# Teensy_PCB.net
KiCad netlist of a schematic drawn in EAGLE
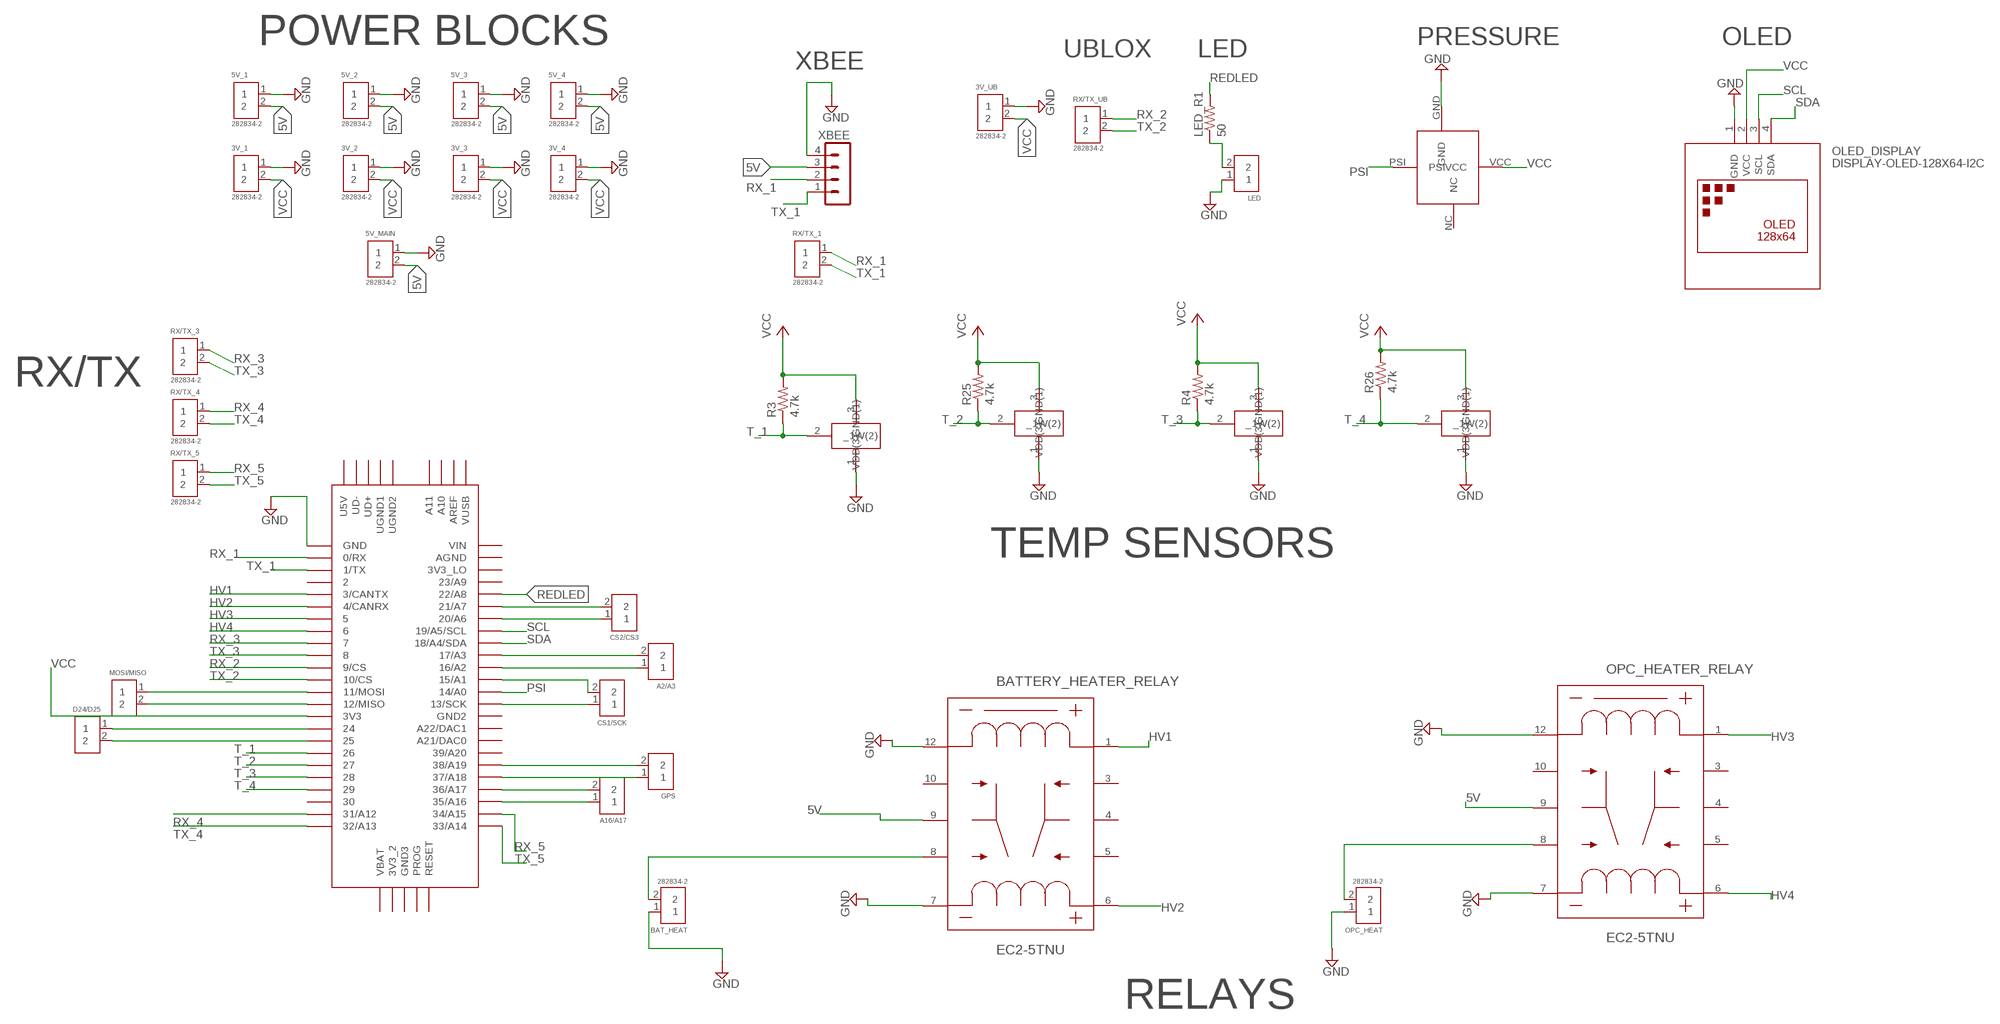
[diagram p0: schematic, sheet 1]

(export (version "E")
  (design (tool "Eeschema 10.0.6"))
  (components
    (comp (ref "3V_1")
      (value "282834-2")
      (footprint "eagle-import:CONN_282834-2")
      (fields (field (name "DIGI-KEY_PART_NUMBER") "A98333-ND") (field (name "MF") "TE Connectivity"))
      (libsource (lib "eagle-import") (part "282834-2"))
    )
    (comp (ref "3V_2")
      (value "282834-2")
      (footprint "eagle-import:CONN_282834-2")
      (fields (field (name "DIGI-KEY_PART_NUMBER") "A98333-ND") (field (name "MF") "TE Connectivity"))
      (libsource (lib "eagle-import") (part "282834-2"))
    )
    (comp (ref "3V_3")
      (value "282834-2")
      (footprint "eagle-import:CONN_282834-2")
      (fields (field (name "DIGI-KEY_PART_NUMBER") "A98333-ND") (field (name "MF") "TE Connectivity"))
      (libsource (lib "eagle-import") (part "282834-2"))
    )
    (comp (ref "3V_4")
      (value "282834-2")
      (footprint "eagle-import:CONN_282834-2")
      (fields (field (name "DIGI-KEY_PART_NUMBER") "A98333-ND") (field (name "MF") "TE Connectivity"))
      (libsource (lib "eagle-import") (part "282834-2"))
    )
    (comp (ref "3V_UB")
      (value "282834-2")
      (footprint "eagle-import:CONN_282834-2")
      (fields (field (name "DIGI-KEY_PART_NUMBER") "A98333-ND") (field (name "MF") "TE Connectivity"))
      (libsource (lib "eagle-import") (part "282834-2"))
    )
    (comp (ref "5V_1")
      (value "282834-2")
      (footprint "eagle-import:CONN_282834-2")
      (fields (field (name "DIGI-KEY_PART_NUMBER") "A98333-ND") (field (name "MF") "TE Connectivity"))
      (libsource (lib "eagle-import") (part "282834-2"))
    )
    (comp (ref "5V_2")
      (value "282834-2")
      (footprint "eagle-import:CONN_282834-2")
      (fields (field (name "DIGI-KEY_PART_NUMBER") "A98333-ND") (field (name "MF") "TE Connectivity"))
      (libsource (lib "eagle-import") (part "282834-2"))
    )
    (comp (ref "5V_3")
      (value "282834-2")
      (footprint "eagle-import:CONN_282834-2")
      (fields (field (name "DIGI-KEY_PART_NUMBER") "A98333-ND") (field (name "MF") "TE Connectivity"))
      (libsource (lib "eagle-import") (part "282834-2"))
    )
    (comp (ref "5V_4")
      (value "282834-2")
      (footprint "eagle-import:CONN_282834-2")
      (fields (field (name "DIGI-KEY_PART_NUMBER") "A98333-ND") (field (name "MF") "TE Connectivity"))
      (libsource (lib "eagle-import") (part "282834-2"))
    )
    (comp (ref "5V_MAIN")
      (value "282834-2")
      (footprint "eagle-import:CONN_282834-2")
      (fields (field (name "DIGI-KEY_PART_NUMBER") "A98333-ND") (field (name "MF") "TE Connectivity"))
      (libsource (lib "eagle-import") (part "282834-2"))
    )
    (comp (ref "A2/A3")
      (value "282834-2")
      (footprint "eagle-import:CONN_282834-2")
      (fields (field (name "DIGI-KEY_PART_NUMBER") "A98333-ND") (field (name "MF") "TE Connectivity"))
      (libsource (lib "eagle-import") (part "282834-2"))
    )
    (comp (ref "A16/A17")
      (value "282834-2")
      (footprint "eagle-import:CONN_282834-2")
      (fields (field (name "DIGI-KEY_PART_NUMBER") "A98333-ND") (field (name "MF") "TE Connectivity"))
      (libsource (lib "eagle-import") (part "282834-2"))
    )
    (comp (ref "BATTERY_HEATER_RELAY")
      (value "EC2-5TNU")
      (footprint "eagle-import:EC2TNU")
      (fields (field (name "MANUFACTURER_PART_NUMBER") "EC25TNU"))
      (libsource (lib "eagle-import") (part "EC2-5TNU"))
    )
    (comp (ref "BAT_HEAT")
      (value "282834-2")
      (footprint "eagle-import:CONN_282834-2")
      (fields (field (name "DIGI-KEY_PART_NUMBER") "A98333-ND") (field (name "MF") "TE Connectivity"))
      (libsource (lib "eagle-import") (part "282834-2"))
    )
    (comp (ref "CS1/SCK")
      (value "282834-2")
      (footprint "eagle-import:CONN_282834-2")
      (fields (field (name "DIGI-KEY_PART_NUMBER") "A98333-ND") (field (name "MF") "TE Connectivity"))
      (libsource (lib "eagle-import") (part "282834-2"))
    )
    (comp (ref "CS2/CS3")
      (value "282834-2")
      (footprint "eagle-import:CONN_282834-2")
      (fields (field (name "DIGI-KEY_PART_NUMBER") "A98333-ND") (field (name "MF") "TE Connectivity"))
      (libsource (lib "eagle-import") (part "282834-2"))
    )
    (comp (ref "D24/D25")
      (value "282834-2")
      (footprint "eagle-import:CONN_282834-2")
      (fields (field (name "DIGI-KEY_PART_NUMBER") "A98333-ND") (field (name "MF") "TE Connectivity"))
      (libsource (lib "eagle-import") (part "282834-2"))
    )
    (comp (ref "GPS")
      (value "282834-2")
      (footprint "eagle-import:CONN_282834-2")
      (fields (field (name "DIGI-KEY_PART_NUMBER") "A98333-ND") (field (name "MF") "TE Connectivity"))
      (libsource (lib "eagle-import") (part "282834-2"))
    )
    (comp (ref "LED")
      (value "282834-2")
      (footprint "eagle-import:CONN_282834-2")
      (fields (field (name "DIGI-KEY_PART_NUMBER") "A98333-ND") (field (name "MF") "TE Connectivity"))
      (libsource (lib "eagle-import") (part "282834-2"))
    )
    (comp (ref "LED_R1")
      (value "50")
      (footprint "eagle-import:0204_7")
      (libsource (lib "eagle-import") (part "R-US_0204/7"))
    )
    (comp (ref "MOSI/MISO")
      (value "282834-2")
      (footprint "eagle-import:CONN_282834-2")
      (fields (field (name "DIGI-KEY_PART_NUMBER") "A98333-ND") (field (name "MF") "TE Connectivity"))
      (libsource (lib "eagle-import") (part "282834-2"))
    )
    (comp (ref "OLED_DISPLAY")
      (value "DISPLAY-OLED-128X64-I2C")
      (footprint "eagle-import:DISPLAY-OLED-128X64-I2C")
      (libsource (lib "eagle-import") (part "DISPLAY-OLED-128X64-I2C"))
    )
    (comp (ref "OPC_HEAT")
      (value "282834-2")
      (footprint "eagle-import:CONN_282834-2")
      (fields (field (name "DIGI-KEY_PART_NUMBER") "A98333-ND") (field (name "MF") "TE Connectivity"))
      (libsource (lib "eagle-import") (part "282834-2"))
    )
    (comp (ref "OPC_HEATER_RELAY")
      (value "EC2-5TNU")
      (footprint "eagle-import:EC2TNU")
      (fields (field (name "MANUFACTURER_PART_NUMBER") "EC25TNU"))
      (libsource (lib "eagle-import") (part "EC2-5TNU"))
    )
    (comp (ref "PRESSURE_SENSOR")
      (value "SSCSANN015PAAA5")
      (footprint "eagle-import:SSCSANN015PAAA5")
      (libsource (lib "eagle-import") (part "SSCSANN015PAAA5"))
    )
    (comp (ref "R3")
      (value "4.7k")
      (footprint "eagle-import:0204_7")
      (libsource (lib "eagle-import") (part "R-US_0204/7"))
    )
    (comp (ref "R4")
      (value "4.7k")
      (footprint "eagle-import:0204_7")
      (libsource (lib "eagle-import") (part "R-US_0204/7"))
    )
    (comp (ref "R25")
      (value "4.7k")
      (footprint "eagle-import:0204_7")
      (libsource (lib "eagle-import") (part "R-US_0204/7"))
    )
    (comp (ref "R26")
      (value "4.7k")
      (footprint "eagle-import:0204_7")
      (libsource (lib "eagle-import") (part "R-US_0204/7"))
    )
    (comp (ref "RX/TX_1")
      (value "282834-2")
      (footprint "eagle-import:CONN_282834-2")
      (fields (field (name "DIGI-KEY_PART_NUMBER") "A98333-ND") (field (name "MF") "TE Connectivity"))
      (libsource (lib "eagle-import") (part "282834-2"))
    )
    (comp (ref "RX/TX_3")
      (value "282834-2")
      (footprint "eagle-import:CONN_282834-2")
      (fields (field (name "DIGI-KEY_PART_NUMBER") "A98333-ND") (field (name "MF") "TE Connectivity"))
      (libsource (lib "eagle-import") (part "282834-2"))
    )
    (comp (ref "RX/TX_4")
      (value "282834-2")
      (footprint "eagle-import:CONN_282834-2")
      (fields (field (name "DIGI-KEY_PART_NUMBER") "A98333-ND") (field (name "MF") "TE Connectivity"))
      (libsource (lib "eagle-import") (part "282834-2"))
    )
    (comp (ref "RX/TX_5")
      (value "282834-2")
      (footprint "eagle-import:CONN_282834-2")
      (fields (field (name "DIGI-KEY_PART_NUMBER") "A98333-ND") (field (name "MF") "TE Connectivity"))
      (libsource (lib "eagle-import") (part "282834-2"))
    )
    (comp (ref "RX/TX_UB")
      (value "282834-2")
      (footprint "eagle-import:CONN_282834-2")
      (fields (field (name "DIGI-KEY_PART_NUMBER") "A98333-ND") (field (name "MF") "TE Connectivity"))
      (libsource (lib "eagle-import") (part "282834-2"))
    )
    (comp (ref "TEMP_1")
      (value "DS18B20.2")
      (footprint "eagle-import:TO92-")
      (libsource (lib "eagle-import") (part "DS18B20.2"))
    )
    (comp (ref "TEMP_2")
      (value "DS18B20.2")
      (footprint "eagle-import:TO92-")
      (libsource (lib "eagle-import") (part "DS18B20.2"))
    )
    (comp (ref "TEMP_3")
      (value "DS18B20.2")
      (footprint "eagle-import:TO92-")
      (libsource (lib "eagle-import") (part "DS18B20.2"))
    )
    (comp (ref "TEMP_4")
      (value "DS18B20.2")
      (footprint "eagle-import:TO92-")
      (libsource (lib "eagle-import") (part "DS18B20.2"))
    )
    (comp (ref "U$1")
      (value "TEENSY_3.5/3.6")
      (footprint "eagle-import:TEENSY_3.5_3.6")
      (libsource (lib "eagle-import") (part "TEENSY_3.5/3.6"))
    )
    (comp (ref "XBEE")
      (value "MA04-1")
      (footprint "eagle-import:MA04-1")
      (libsource (lib "eagle-import") (part "MA04-1"))
    )
  )
  (nets
    (net (code "1") (name "/HV1") (class "Default")
      (node (ref "BATTERY_HEATER_RELAY") (pin "1") (pinfunction "1_1") (pintype "passive"))
      (node (ref "U$1") (pin "3/CANTX") (pinfunction "3/CANTX_3/CANTX") (pintype "bidirectional"))
    )
    (net (code "2") (name "/HV2") (class "Default")
      (node (ref "BATTERY_HEATER_RELAY") (pin "6") (pinfunction "5_6") (pintype "passive"))
      (node (ref "U$1") (pin "4/CANRX") (pinfunction "4/CANRX_4/CANRX") (pintype "bidirectional"))
    )
    (net (code "3") (name "/HV3") (class "Default")
      (node (ref "OPC_HEATER_RELAY") (pin "1") (pinfunction "1_1") (pintype "passive"))
      (node (ref "U$1") (pin "5") (pinfunction "5_5") (pintype "bidirectional"))
    )
    (net (code "4") (name "/HV4") (class "Default")
      (node (ref "OPC_HEATER_RELAY") (pin "6") (pinfunction "5_6") (pintype "passive"))
      (node (ref "U$1") (pin "6") (pinfunction "6_6") (pintype "bidirectional"))
    )
    (net (code "5") (name "/PSI") (class "Default")
      (node (ref "PRESSURE_SENSOR") (pin "PSI") (pinfunction "PSI_PSI") (pintype "bidirectional"))
      (node (ref "U$1") (pin "14/A0") (pinfunction "14/A0_14/A0") (pintype "bidirectional"))
    )
    (net (code "6") (name "/RX_1") (class "Default")
      (node (ref "RX/TX_1") (pin "1") (pinfunction "1_1") (pintype "passive"))
      (node (ref "U$1") (pin "0/RX") (pinfunction "0/RX_0/RX") (pintype "bidirectional"))
      (node (ref "XBEE") (pin "2") (pinfunction "2_2") (pintype "passive"))
    )
    (net (code "7") (name "/RX_2") (class "Default")
      (node (ref "RX/TX_UB") (pin "1") (pinfunction "1_1") (pintype "passive"))
      (node (ref "U$1") (pin "9/CS") (pinfunction "9/CS_9/CS") (pintype "bidirectional"))
    )
    (net (code "8") (name "/RX_3") (class "Default")
      (node (ref "RX/TX_3") (pin "1") (pinfunction "1_1") (pintype "passive"))
      (node (ref "U$1") (pin "7") (pinfunction "7_7") (pintype "bidirectional"))
    )
    (net (code "9") (name "/RX_4") (class "Default")
      (node (ref "RX/TX_4") (pin "1") (pinfunction "1_1") (pintype "passive"))
      (node (ref "U$1") (pin "31/A12") (pinfunction "31/A12_31/A12") (pintype "bidirectional"))
    )
    (net (code "10") (name "/RX_5") (class "Default")
      (node (ref "RX/TX_5") (pin "1") (pinfunction "1_1") (pintype "passive"))
      (node (ref "U$1") (pin "34/A15") (pinfunction "34/A15_34/A15") (pintype "bidirectional"))
    )
    (net (code "11") (name "/SCL") (class "Default")
      (node (ref "OLED_DISPLAY") (pin "3") (pinfunction "SCL_3") (pintype "bidirectional"))
      (node (ref "U$1") (pin "19/A5/SCL") (pinfunction "19/A5/SCL_19/A5/SCL") (pintype "bidirectional"))
    )
    (net (code "12") (name "/SDA") (class "Default")
      (node (ref "OLED_DISPLAY") (pin "4") (pinfunction "SDA_4") (pintype "bidirectional"))
      (node (ref "U$1") (pin "18/A4/SDA") (pinfunction "18/A4/SDA_18/A4/SDA") (pintype "bidirectional"))
    )
    (net (code "13") (name "/TX_1") (class "Default")
      (node (ref "RX/TX_1") (pin "2") (pinfunction "2_2") (pintype "passive"))
      (node (ref "U$1") (pin "1/TX") (pinfunction "1/TX_1/TX") (pintype "bidirectional"))
      (node (ref "XBEE") (pin "1") (pinfunction "1_1") (pintype "passive"))
    )
    (net (code "14") (name "/TX_2") (class "Default")
      (node (ref "RX/TX_UB") (pin "2") (pinfunction "2_2") (pintype "passive"))
      (node (ref "U$1") (pin "10/CS") (pinfunction "10/CS_10/CS") (pintype "bidirectional"))
    )
    (net (code "15") (name "/TX_3") (class "Default")
      (node (ref "RX/TX_3") (pin "2") (pinfunction "2_2") (pintype "passive"))
      (node (ref "U$1") (pin "8") (pinfunction "8_8") (pintype "bidirectional"))
    )
    (net (code "16") (name "/TX_4") (class "Default")
      (node (ref "RX/TX_4") (pin "2") (pinfunction "2_2") (pintype "passive"))
      (node (ref "U$1") (pin "32/A13") (pinfunction "32/A13_32/A13") (pintype "bidirectional"))
    )
    (net (code "17") (name "/TX_5") (class "Default")
      (node (ref "RX/TX_5") (pin "2") (pinfunction "2_2") (pintype "passive"))
      (node (ref "U$1") (pin "33/A14") (pinfunction "33/A14_33/A14") (pintype "bidirectional"))
    )
    (net (code "18") (name "/T_1") (class "Default")
      (node (ref "R3") (pin "1") (pinfunction "1_1") (pintype "passive"))
      (node (ref "TEMP_1") (pin "2") (pinfunction "_1W(2)_2") (pintype "bidirectional"))
      (node (ref "U$1") (pin "26") (pinfunction "26_26") (pintype "bidirectional"))
    )
    (net (code "19") (name "/T_2") (class "Default")
      (node (ref "R25") (pin "1") (pinfunction "1_1") (pintype "passive"))
      (node (ref "TEMP_2") (pin "2") (pinfunction "_1W(2)_2") (pintype "bidirectional"))
      (node (ref "U$1") (pin "27") (pinfunction "27_27") (pintype "bidirectional"))
    )
    (net (code "20") (name "/T_3") (class "Default")
      (node (ref "R4") (pin "1") (pinfunction "1_1") (pintype "passive"))
      (node (ref "TEMP_3") (pin "2") (pinfunction "_1W(2)_2") (pintype "bidirectional"))
      (node (ref "U$1") (pin "28") (pinfunction "28_28") (pintype "bidirectional"))
    )
    (net (code "21") (name "/T_4") (class "Default")
      (node (ref "R26") (pin "1") (pinfunction "1_1") (pintype "passive"))
      (node (ref "TEMP_4") (pin "2") (pinfunction "_1W(2)_2") (pintype "bidirectional"))
      (node (ref "U$1") (pin "29") (pinfunction "29_29") (pintype "bidirectional"))
    )
    (net (code "22") (name "5V") (class "Default")
      (node (ref "5V_1") (pin "2") (pinfunction "2_2") (pintype "passive"))
      (node (ref "5V_2") (pin "2") (pinfunction "2_2") (pintype "passive"))
      (node (ref "5V_3") (pin "2") (pinfunction "2_2") (pintype "passive"))
      (node (ref "5V_4") (pin "2") (pinfunction "2_2") (pintype "passive"))
      (node (ref "5V_MAIN") (pin "2") (pinfunction "2_2") (pintype "passive"))
      (node (ref "BATTERY_HEATER_RELAY") (pin "9") (pinfunction "8_9") (pintype "passive"))
      (node (ref "OPC_HEATER_RELAY") (pin "9") (pinfunction "8_9") (pintype "passive"))
      (node (ref "XBEE") (pin "3") (pinfunction "3_3") (pintype "passive"))
    )
    (net (code "23") (name "GND") (class "Default")
      (node (ref "3V_1") (pin "1") (pinfunction "1_1") (pintype "passive"))
      (node (ref "3V_2") (pin "1") (pinfunction "1_1") (pintype "passive"))
      (node (ref "3V_3") (pin "1") (pinfunction "1_1") (pintype "passive"))
      (node (ref "3V_4") (pin "1") (pinfunction "1_1") (pintype "passive"))
      (node (ref "3V_UB") (pin "1") (pinfunction "1_1") (pintype "passive"))
      (node (ref "5V_1") (pin "1") (pinfunction "1_1") (pintype "passive"))
      (node (ref "5V_2") (pin "1") (pinfunction "1_1") (pintype "passive"))
      (node (ref "5V_3") (pin "1") (pinfunction "1_1") (pintype "passive"))
      (node (ref "5V_4") (pin "1") (pinfunction "1_1") (pintype "passive"))
      (node (ref "5V_MAIN") (pin "1") (pinfunction "1_1") (pintype "passive"))
      (node (ref "BATTERY_HEATER_RELAY") (pin "12") (pinfunction "10_12") (pintype "passive"))
      (node (ref "BATTERY_HEATER_RELAY") (pin "7") (pinfunction "6_7") (pintype "passive"))
      (node (ref "BAT_HEAT") (pin "1") (pinfunction "1_1") (pintype "passive"))
      (node (ref "LED") (pin "1") (pinfunction "1_1") (pintype "passive"))
      (node (ref "OLED_DISPLAY") (pin "1") (pinfunction "GND_1") (pintype "power_in"))
      (node (ref "OPC_HEAT") (pin "1") (pinfunction "1_1") (pintype "passive"))
      (node (ref "OPC_HEATER_RELAY") (pin "12") (pinfunction "10_12") (pintype "passive"))
      (node (ref "OPC_HEATER_RELAY") (pin "7") (pinfunction "6_7") (pintype "passive"))
      (node (ref "PRESSURE_SENSOR") (pin "GND") (pinfunction "GND_GND") (pintype "bidirectional"))
      (node (ref "TEMP_1") (pin "1") (pinfunction "GND(1)_1") (pintype "bidirectional"))
      (node (ref "TEMP_2") (pin "1") (pinfunction "GND(1)_1") (pintype "bidirectional"))
      (node (ref "TEMP_3") (pin "1") (pinfunction "GND(1)_1") (pintype "bidirectional"))
      (node (ref "TEMP_4") (pin "1") (pinfunction "GND(1)_1") (pintype "bidirectional"))
      (node (ref "U$1") (pin "GND") (pinfunction "GND_GND") (pintype "bidirectional"))
      (node (ref "XBEE") (pin "4") (pinfunction "4_4") (pintype "passive"))
    )
    (net (code "24") (name "Net-(A2/A3-Pad1)") (class "Default")
      (node (ref "A2/A3") (pin "1") (pinfunction "1_1") (pintype "passive"))
      (node (ref "U$1") (pin "16/A2") (pinfunction "16/A2_16/A2") (pintype "bidirectional"))
    )
    (net (code "25") (name "Net-(A2/A3-Pad2)") (class "Default")
      (node (ref "A2/A3") (pin "2") (pinfunction "2_2") (pintype "passive"))
      (node (ref "U$1") (pin "17/A3") (pinfunction "17/A3_17/A3") (pintype "bidirectional"))
    )
    (net (code "26") (name "Net-(A16/A17-Pad1)") (class "Default")
      (node (ref "A16/A17") (pin "1") (pinfunction "1_1") (pintype "passive"))
      (node (ref "U$1") (pin "35/A16") (pinfunction "35/A16_35/A16") (pintype "bidirectional"))
    )
    (net (code "27") (name "Net-(A16/A17-Pad2)") (class "Default")
      (node (ref "A16/A17") (pin "2") (pinfunction "2_2") (pintype "passive"))
      (node (ref "U$1") (pin "36/A17") (pinfunction "36/A17_36/A17") (pintype "bidirectional"))
    )
    (net (code "28") (name "Net-(BATTERY_HEATER_RELAY-7)") (class "Default")
      (node (ref "BATTERY_HEATER_RELAY") (pin "8") (pinfunction "7_8") (pintype "passive"))
      (node (ref "BAT_HEAT") (pin "2") (pinfunction "2_2") (pintype "passive"))
    )
    (net (code "29") (name "Net-(CS1/SCK-Pad1)") (class "Default")
      (node (ref "CS1/SCK") (pin "1") (pinfunction "1_1") (pintype "passive"))
      (node (ref "U$1") (pin "13/SCK") (pinfunction "13/SCK_13/SCK") (pintype "bidirectional"))
    )
    (net (code "30") (name "Net-(CS1/SCK-Pad2)") (class "Default")
      (node (ref "CS1/SCK") (pin "2") (pinfunction "2_2") (pintype "passive"))
      (node (ref "U$1") (pin "15/A1") (pinfunction "15/A1_15/A1") (pintype "bidirectional"))
    )
    (net (code "31") (name "Net-(CS2/CS3-Pad1)") (class "Default")
      (node (ref "CS2/CS3") (pin "1") (pinfunction "1_1") (pintype "passive"))
      (node (ref "U$1") (pin "20/A6") (pinfunction "20/A6_20/A6") (pintype "bidirectional"))
    )
    (net (code "32") (name "Net-(CS2/CS3-Pad2)") (class "Default")
      (node (ref "CS2/CS3") (pin "2") (pinfunction "2_2") (pintype "passive"))
      (node (ref "U$1") (pin "21/A7") (pinfunction "21/A7_21/A7") (pintype "bidirectional"))
    )
    (net (code "33") (name "Net-(D24/D25-Pad1)") (class "Default")
      (node (ref "D24/D25") (pin "1") (pinfunction "1_1") (pintype "passive"))
      (node (ref "U$1") (pin "24") (pinfunction "24_24") (pintype "bidirectional"))
    )
    (net (code "34") (name "Net-(D24/D25-Pad2)") (class "Default")
      (node (ref "D24/D25") (pin "2") (pinfunction "2_2") (pintype "passive"))
      (node (ref "U$1") (pin "25") (pinfunction "25_25") (pintype "bidirectional"))
    )
    (net (code "35") (name "Net-(GPS-Pad1)") (class "Default")
      (node (ref "GPS") (pin "1") (pinfunction "1_1") (pintype "passive"))
      (node (ref "U$1") (pin "37/A18") (pinfunction "37/A18_37/A18") (pintype "bidirectional"))
    )
    (net (code "36") (name "Net-(GPS-Pad2)") (class "Default")
      (node (ref "GPS") (pin "2") (pinfunction "2_2") (pintype "passive"))
      (node (ref "U$1") (pin "38/A19") (pinfunction "38/A19_38/A19") (pintype "bidirectional"))
    )
    (net (code "37") (name "Net-(LED-Pad2)") (class "Default")
      (node (ref "LED") (pin "2") (pinfunction "2_2") (pintype "passive"))
      (node (ref "LED_R1") (pin "1") (pinfunction "1_1") (pintype "passive"))
    )
    (net (code "38") (name "Net-(MOSI/MISO-Pad1)") (class "Default")
      (node (ref "MOSI/MISO") (pin "1") (pinfunction "1_1") (pintype "passive"))
      (node (ref "U$1") (pin "11/MOSI") (pinfunction "11/MOSI_11/MOSI") (pintype "bidirectional"))
    )
    (net (code "39") (name "Net-(MOSI/MISO-Pad2)") (class "Default")
      (node (ref "MOSI/MISO") (pin "2") (pinfunction "2_2") (pintype "passive"))
      (node (ref "U$1") (pin "12/MISO") (pinfunction "12/MISO_12/MISO") (pintype "bidirectional"))
    )
    (net (code "40") (name "Net-(OPC_HEATER_RELAY-7)") (class "Default")
      (node (ref "OPC_HEAT") (pin "2") (pinfunction "2_2") (pintype "passive"))
      (node (ref "OPC_HEATER_RELAY") (pin "8") (pinfunction "7_8") (pintype "passive"))
    )
    (net (code "41") (name "REDLED") (class "Default")
      (node (ref "LED_R1") (pin "2") (pinfunction "2_2") (pintype "passive"))
      (node (ref "U$1") (pin "22/A8") (pinfunction "22/A8_22/A8") (pintype "bidirectional"))
    )
    (net (code "42") (name "VCC") (class "Default")
      (node (ref "3V_1") (pin "2") (pinfunction "2_2") (pintype "passive"))
      (node (ref "3V_2") (pin "2") (pinfunction "2_2") (pintype "passive"))
      (node (ref "3V_3") (pin "2") (pinfunction "2_2") (pintype "passive"))
      (node (ref "3V_4") (pin "2") (pinfunction "2_2") (pintype "passive"))
      (node (ref "3V_UB") (pin "2") (pinfunction "2_2") (pintype "passive"))
      (node (ref "OLED_DISPLAY") (pin "2") (pinfunction "VCC_2") (pintype "power_in"))
      (node (ref "PRESSURE_SENSOR") (pin "VCC") (pinfunction "VCC_VCC") (pintype "bidirectional"))
      (node (ref "R25") (pin "2") (pinfunction "2_2") (pintype "passive"))
      (node (ref "R26") (pin "2") (pinfunction "2_2") (pintype "passive"))
      (node (ref "R3") (pin "2") (pinfunction "2_2") (pintype "passive"))
      (node (ref "R4") (pin "2") (pinfunction "2_2") (pintype "passive"))
      (node (ref "TEMP_1") (pin "3") (pinfunction "VDD(3)_3") (pintype "bidirectional"))
      (node (ref "TEMP_2") (pin "3") (pinfunction "VDD(3)_3") (pintype "bidirectional"))
      (node (ref "TEMP_3") (pin "3") (pinfunction "VDD(3)_3") (pintype "bidirectional"))
      (node (ref "TEMP_4") (pin "3") (pinfunction "VDD(3)_3") (pintype "bidirectional"))
      (node (ref "U$1") (pin "3V3") (pinfunction "3V3_3V3") (pintype "bidirectional"))
    )
    (net (code "43") (name "unconnected-(BATTERY_HEATER_RELAY-2-Pad3)") (class "Default")
      (node (ref "BATTERY_HEATER_RELAY") (pin "3") (pinfunction "2_3") (pintype "passive"))
    )
    (net (code "44") (name "unconnected-(BATTERY_HEATER_RELAY-3-Pad4)") (class "Default")
      (node (ref "BATTERY_HEATER_RELAY") (pin "4") (pinfunction "3_4") (pintype "passive"))
    )
    (net (code "45") (name "unconnected-(BATTERY_HEATER_RELAY-4-Pad5)") (class "Default")
      (node (ref "BATTERY_HEATER_RELAY") (pin "5") (pinfunction "4_5") (pintype "passive"))
    )
    (net (code "46") (name "unconnected-(BATTERY_HEATER_RELAY-9-Pad10)") (class "Default")
      (node (ref "BATTERY_HEATER_RELAY") (pin "10") (pinfunction "9_10") (pintype "passive"))
    )
    (net (code "47") (name "unconnected-(OPC_HEATER_RELAY-2-Pad3)") (class "Default")
      (node (ref "OPC_HEATER_RELAY") (pin "3") (pinfunction "2_3") (pintype "passive"))
    )
    (net (code "48") (name "unconnected-(OPC_HEATER_RELAY-3-Pad4)") (class "Default")
      (node (ref "OPC_HEATER_RELAY") (pin "4") (pinfunction "3_4") (pintype "passive"))
    )
    (net (code "49") (name "unconnected-(OPC_HEATER_RELAY-4-Pad5)") (class "Default")
      (node (ref "OPC_HEATER_RELAY") (pin "5") (pinfunction "4_5") (pintype "passive"))
    )
    (net (code "50") (name "unconnected-(OPC_HEATER_RELAY-9-Pad10)") (class "Default")
      (node (ref "OPC_HEATER_RELAY") (pin "10") (pinfunction "9_10") (pintype "passive"))
    )
    (net (code "51") (name "unconnected-(PRESSURE_SENSOR-PadNC)") (class "Default")
      (node (ref "PRESSURE_SENSOR") (pin "NC") (pinfunction "NC_NC") (pintype "bidirectional"))
    )
    (net (code "52") (name "unconnected-(U$1-A21{slash}DAC0-Pad21{slash}DAC0)") (class "Default")
      (node (ref "U$1") (pin "21/DAC0") (pinfunction "A21/DAC0_21/DAC0") (pintype "bidirectional"))
    )
    (net (code "53") (name "unconnected-(U$1-Pad2)") (class "Default")
      (node (ref "U$1") (pin "2") (pinfunction "2_2") (pintype "bidirectional"))
    )
    (net (code "54") (name "unconnected-(U$1-Pad3V3_2)") (class "Default")
      (node (ref "U$1") (pin "3V3_2") (pinfunction "3V3_2_3V3_2") (pintype "bidirectional"))
    )
    (net (code "55") (name "unconnected-(U$1-Pad3V3_LO)") (class "Default")
      (node (ref "U$1") (pin "3V3_LO") (pinfunction "3V3_LO_3V3_LO") (pintype "bidirectional"))
    )
    (net (code "56") (name "unconnected-(U$1-Pad23{slash}A9)") (class "Default")
      (node (ref "U$1") (pin "23/A9") (pinfunction "23/A9_23/A9") (pintype "bidirectional"))
    )
    (net (code "57") (name "unconnected-(U$1-Pad30)") (class "Default")
      (node (ref "U$1") (pin "30") (pinfunction "30_30") (pintype "bidirectional"))
    )
    (net (code "58") (name "unconnected-(U$1-Pad39{slash}A20)") (class "Default")
      (node (ref "U$1") (pin "39/A20") (pinfunction "39/A20_39/A20") (pintype "bidirectional"))
    )
    (net (code "59") (name "unconnected-(U$1-PadA10)") (class "Default")
      (node (ref "U$1") (pin "A10") (pinfunction "A10_A10") (pintype "bidirectional"))
    )
    (net (code "60") (name "unconnected-(U$1-PadA11)") (class "Default")
      (node (ref "U$1") (pin "A11") (pinfunction "A11_A11") (pintype "bidirectional"))
    )
    (net (code "61") (name "unconnected-(U$1-PadA22{slash}DAC1)") (class "Default")
      (node (ref "U$1") (pin "A22/DAC1") (pinfunction "A22/DAC1_A22/DAC1") (pintype "bidirectional"))
    )
    (net (code "62") (name "unconnected-(U$1-PadAGND)") (class "Default")
      (node (ref "U$1") (pin "AGND") (pinfunction "AGND_AGND") (pintype "bidirectional"))
    )
    (net (code "63") (name "unconnected-(U$1-PadAREF)") (class "Default")
      (node (ref "U$1") (pin "AREF") (pinfunction "AREF_AREF") (pintype "bidirectional"))
    )
    (net (code "64") (name "unconnected-(U$1-PadGND2)") (class "Default")
      (node (ref "U$1") (pin "GND2") (pinfunction "GND2_GND2") (pintype "bidirectional"))
    )
    (net (code "65") (name "unconnected-(U$1-PadGND3)") (class "Default")
      (node (ref "U$1") (pin "GND3") (pinfunction "GND3_GND3") (pintype "bidirectional"))
    )
    (net (code "66") (name "unconnected-(U$1-PadPROG)") (class "Default")
      (node (ref "U$1") (pin "PROG") (pinfunction "PROG_PROG") (pintype "bidirectional"))
    )
    (net (code "67") (name "unconnected-(U$1-PadRESET)") (class "Default")
      (node (ref "U$1") (pin "RESET") (pinfunction "RESET_RESET") (pintype "bidirectional"))
    )
    (net (code "68") (name "unconnected-(U$1-PadU5V)") (class "Default")
      (node (ref "U$1") (pin "U5V") (pinfunction "U5V_U5V") (pintype "bidirectional"))
    )
    (net (code "69") (name "unconnected-(U$1-PadUD+)") (class "Default")
      (node (ref "U$1") (pin "UD+") (pinfunction "UD+_UD+") (pintype "bidirectional"))
    )
    (net (code "70") (name "unconnected-(U$1-PadUD-)") (class "Default")
      (node (ref "U$1") (pin "UD-") (pinfunction "UD-_UD-") (pintype "bidirectional"))
    )
    (net (code "71") (name "unconnected-(U$1-PadUGND1)") (class "Default")
      (node (ref "U$1") (pin "UGND1") (pinfunction "UGND1_UGND1") (pintype "bidirectional"))
    )
    (net (code "72") (name "unconnected-(U$1-PadUGND2)") (class "Default")
      (node (ref "U$1") (pin "UGND2") (pinfunction "UGND2_UGND2") (pintype "bidirectional"))
    )
    (net (code "73") (name "unconnected-(U$1-PadVBAT)") (class "Default")
      (node (ref "U$1") (pin "VBAT") (pinfunction "VBAT_VBAT") (pintype "bidirectional"))
    )
    (net (code "74") (name "unconnected-(U$1-PadVIN)") (class "Default")
      (node (ref "U$1") (pin "VIN") (pinfunction "VIN_VIN") (pintype "bidirectional"))
    )
    (net (code "75") (name "unconnected-(U$1-PadVUSB)") (class "Default")
      (node (ref "U$1") (pin "VUSB") (pinfunction "VUSB_VUSB") (pintype "bidirectional"))
    )
  )
)
